# ProPrj_Analog_AI_Accelerator_2026-06-26.net
KiCad netlist of a schematic drawn in EasyEDA Pro
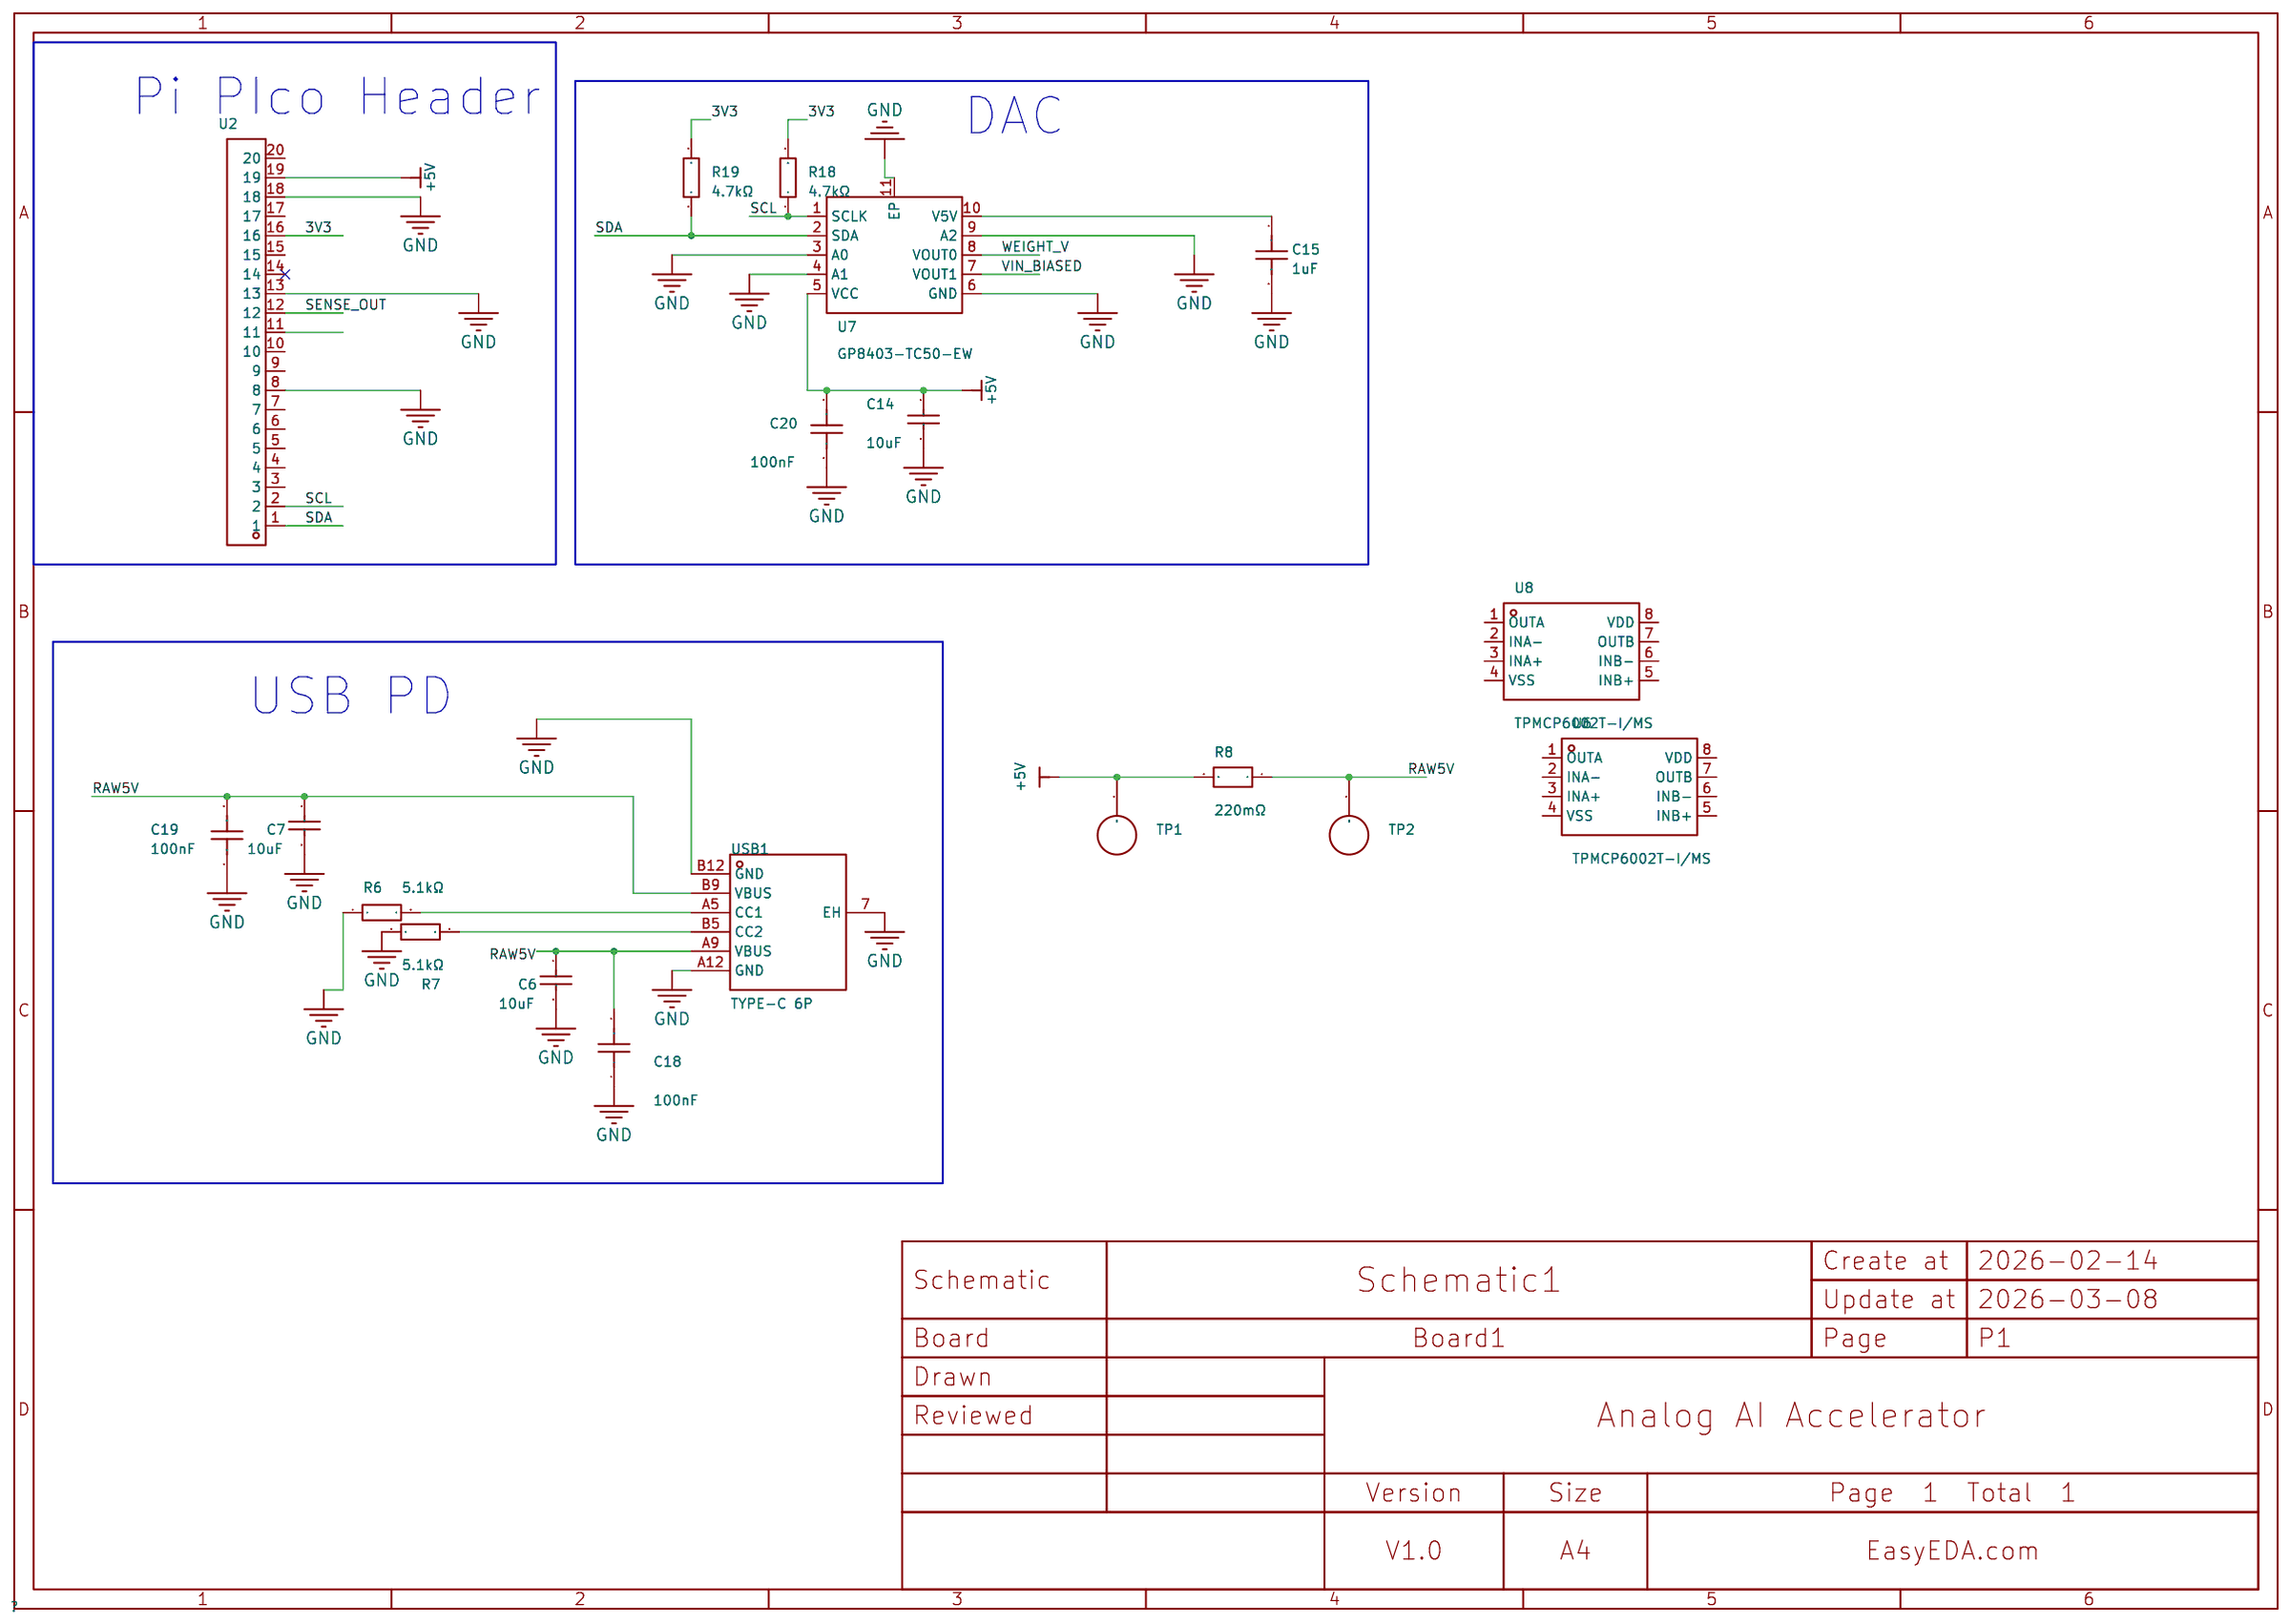
[diagram p0: schematic sheet]

(export (version "E")
  (design (tool "Eeschema 10.0.6"))
  (components
    (comp (ref "C6")
      (value "10uF")
      (footprint "easyedapro:C1206")
      (fields
        (field (name "Manufacturer Part") "CL31A106KBHNNNE")
        (field (name "Manufacturer") "SAMSUNG(三星)")
      )
      (libsource (lib "easyedapro") (part "CL31A106KBHNNNE"))
    )
    (comp (ref "C7")
      (value "10uF")
      (footprint "easyedapro:C1206")
      (fields
        (field (name "Manufacturer Part") "CL31A106KBHNNNE")
        (field (name "Manufacturer") "SAMSUNG(三星)")
      )
      (libsource (lib "easyedapro") (part "CL31A106KBHNNNE"))
    )
    (comp (ref "C14")
      (value "10uF")
      (footprint "easyedapro:C1206")
      (fields
        (field (name "Manufacturer Part") "CL31A106KBHNNNE")
        (field (name "Manufacturer") "SAMSUNG(三星)")
      )
      (libsource (lib "easyedapro") (part "CL31A106KBHNNNE"))
    )
    (comp (ref "C15")
      (value "1uF")
      (footprint "easyedapro:C1206")
      (fields
        (field (name "Manufacturer Part") "CL31B105KBHNNNE")
        (field (name "Manufacturer") "SAMSUNG(三星)")
      )
      (libsource (lib "easyedapro") (part "CL31B105KBHNNNE"))
    )
    (comp (ref "C18")
      (value "100nF")
      (footprint "easyedapro:C0603")
      (fields
        (field (name "Manufacturer Part") "CC0603KRX7R9BB104")
        (field (name "Manufacturer") "YAGEO(国巨)")
      )
      (libsource (lib "easyedapro") (part "CC0603KRX7R9BB104"))
    )
    (comp (ref "C19")
      (value "100nF")
      (footprint "easyedapro:C0603")
      (fields
        (field (name "Manufacturer Part") "CC0603KRX7R9BB104")
        (field (name "Manufacturer") "YAGEO(国巨)")
      )
      (libsource (lib "easyedapro") (part "CC0603KRX7R9BB104"))
    )
    (comp (ref "C20")
      (value "100nF")
      (footprint "easyedapro:C0603")
      (fields
        (field (name "Manufacturer Part") "CC0603KRX7R9BB104")
        (field (name "Manufacturer") "YAGEO(国巨)")
      )
      (libsource (lib "easyedapro") (part "CC0603KRX7R9BB104"))
    )
    (comp (ref "R6")
      (value "5.1kΩ")
      (footprint "easyedapro:R0603")
      (fields
        (field (name "Manufacturer Part") "0603WAF5101T5E")
        (field (name "Manufacturer") "UNI-ROYAL(厚声)")
      )
      (libsource (lib "easyedapro") (part "0603WAF5101T5E"))
    )
    (comp (ref "R7")
      (value "5.1kΩ")
      (footprint "easyedapro:R0603")
      (fields
        (field (name "Manufacturer Part") "0603WAF5101T5E")
        (field (name "Manufacturer") "UNI-ROYAL(厚声)")
      )
      (libsource (lib "easyedapro") (part "0603WAF5101T5E"))
    )
    (comp (ref "R8")
      (value "220mΩ")
      (footprint "easyedapro:RES-SMD_L6.4-W3.2-1")
      (fields
        (field (name "Manufacturer Part") "HoJLR2512-3W-220mR-1%")
        (field (name "Manufacturer") "Milliohm(毫欧)")
      )
      (libsource (lib "easyedapro") (part "HOJLR2512-3W-220MR-1%"))
    )
    (comp (ref "R18")
      (value "4.7kΩ")
      (footprint "easyedapro:R0805")
      (fields
        (field (name "Manufacturer Part") "0805W8F4701T5E")
        (field (name "Manufacturer") "UNI-ROYAL(厚声)")
      )
      (libsource (lib "easyedapro") (part "0805W8F4701T5E"))
    )
    (comp (ref "R19")
      (value "4.7kΩ")
      (footprint "easyedapro:R0805")
      (fields
        (field (name "Manufacturer Part") "0805W8F4701T5E")
        (field (name "Manufacturer") "UNI-ROYAL(厚声)")
      )
      (libsource (lib "easyedapro") (part "0805W8F4701T5E"))
    )
    (comp (ref "TP1")
      (value "~")
      (footprint "easyedapro:TEST PAD")
      (libsource (lib "easyedapro") (part "TEST PAD"))
    )
    (comp (ref "TP2")
      (value "~")
      (footprint "easyedapro:TEST PAD")
      (libsource (lib "easyedapro") (part "TEST PAD"))
    )
    (comp (ref "U2")
      (value "ZX-PM2.54-1-20PY")
      (footprint "easyedapro:HDR-TH_20P-P2.54-V-F")
      (fields (field (name "Manufacturer") "Megastar(兆星)"))
      (libsource (lib "easyedapro") (part "ZX-PM2.54-1-20PY"))
    )
    (comp (ref "U6")
      (value "TPMCP6002T-I/MS")
      (footprint "easyedapro:MSOP-8_L3.0-W3.0-P0.65-LS4.9-BL")
      (fields (field (name "Manufacturer") "TECH PUBLIC(台舟)"))
      (libsource (lib "easyedapro") (part "TPMCP6002T-I/MS"))
    )
    (comp (ref "U7")
      (value "GP8403-TC50-EW")
      (footprint "easyedapro:ESSOP-10_L4.9-W3.9-P1.00-LS6.0-BL-EP")
      (fields (field (name "Manufacturer") "Guestgood(客益)"))
      (libsource (lib "easyedapro") (part "GP8403-TC50-EW_C3152007"))
    )
    (comp (ref "U8")
      (value "TPMCP6002T-I/MS")
      (footprint "easyedapro:MSOP-8_L3.0-W3.0-P0.65-LS4.9-BL")
      (fields (field (name "Manufacturer") "TECH PUBLIC(台舟)"))
      (libsource (lib "easyedapro") (part "TPMCP6002T-I/MS"))
    )
    (comp (ref "USB1")
      (value "TYPE-C 6P")
      (footprint "easyedapro:TYPE-C-SMD_TYPE-C-6P")
      (fields (field (name "Manufacturer") "SHOU HAN(首韩)"))
      (libsource (lib "easyedapro") (part "TYPE-C 6P"))
    )
  )
  (nets
    (net (code "1") (name "+5V") (class "Default")
      (node (ref "C14") (pin "1") (pinfunction "1_1") (pintype "input"))
      (node (ref "C20") (pin "2") (pinfunction "2_2") (pintype "unspecified"))
      (node (ref "R8") (pin "2") (pinfunction "2_2") (pintype "unspecified"))
      (node (ref "TP1") (pin "1") (pinfunction "TEST_PAD1_1") (pintype "input"))
      (node (ref "U2") (pin "19") (pinfunction "19_19") (pintype "unspecified"))
      (node (ref "U7") (pin "5") (pinfunction "VCC_5") (pintype "unspecified"))
    )
    (net (code "2") (name "/3V3") (class "Default")
      (node (ref "R18") (pin "2") (pinfunction "2_2") (pintype "input"))
      (node (ref "R19") (pin "2") (pinfunction "2_2") (pintype "input"))
      (node (ref "U2") (pin "16") (pinfunction "16_16") (pintype "unspecified"))
    )
    (net (code "3") (name "/RAW5V") (class "Default")
      (node (ref "C18") (pin "2") (pinfunction "2_2") (pintype "unspecified"))
      (node (ref "C19") (pin "2") (pinfunction "2_2") (pintype "unspecified"))
      (node (ref "C6") (pin "1") (pinfunction "1_1") (pintype "input"))
      (node (ref "C7") (pin "1") (pinfunction "1_1") (pintype "input"))
      (node (ref "R8") (pin "1") (pinfunction "1_1") (pintype "unspecified"))
      (node (ref "TP2") (pin "1") (pinfunction "TEST_PAD1_1") (pintype "input"))
      (node (ref "USB1") (pin "A9") (pinfunction "VBUS_A9") (pintype "unspecified"))
      (node (ref "USB1") (pin "B9") (pinfunction "VBUS_B9") (pintype "unspecified"))
    )
    (net (code "4") (name "/SCL") (class "Default")
      (node (ref "R18") (pin "1") (pinfunction "1_1") (pintype "input"))
      (node (ref "U2") (pin "2") (pinfunction "2_2") (pintype "unspecified"))
      (node (ref "U7") (pin "1") (pinfunction "SCLK_1") (pintype "unspecified"))
    )
    (net (code "5") (name "/SDA") (class "Default")
      (node (ref "R19") (pin "1") (pinfunction "1_1") (pintype "input"))
      (node (ref "U2") (pin "1") (pinfunction "1_1") (pintype "unspecified"))
      (node (ref "U7") (pin "2") (pinfunction "SDA_2") (pintype "unspecified"))
    )
    (net (code "6") (name "/SENSE_OUT") (class "Default")
      (node (ref "U2") (pin "12") (pinfunction "12_12") (pintype "unspecified"))
    )
    (net (code "7") (name "/VIN_BIASED") (class "Default")
      (node (ref "U7") (pin "7") (pinfunction "VOUT1_7") (pintype "unspecified"))
    )
    (net (code "8") (name "/WEIGHT_V") (class "Default")
      (node (ref "U7") (pin "8") (pinfunction "VOUT0_8") (pintype "unspecified"))
    )
    (net (code "9") (name "GND") (class "Default")
      (node (ref "C14") (pin "2") (pinfunction "2_2") (pintype "input"))
      (node (ref "C15") (pin "2") (pinfunction "2_2") (pintype "unspecified"))
      (node (ref "C18") (pin "1") (pinfunction "1_1") (pintype "unspecified"))
      (node (ref "C19") (pin "1") (pinfunction "1_1") (pintype "unspecified"))
      (node (ref "C20") (pin "1") (pinfunction "1_1") (pintype "unspecified"))
      (node (ref "C6") (pin "2") (pinfunction "2_2") (pintype "input"))
      (node (ref "C7") (pin "2") (pinfunction "2_2") (pintype "input"))
      (node (ref "R6") (pin "1") (pinfunction "1_1") (pintype "input"))
      (node (ref "R7") (pin "1") (pinfunction "1_1") (pintype "input"))
      (node (ref "U2") (pin "13") (pinfunction "13_13") (pintype "unspecified"))
      (node (ref "U2") (pin "18") (pinfunction "18_18") (pintype "unspecified"))
      (node (ref "U2") (pin "8") (pinfunction "8_8") (pintype "unspecified"))
      (node (ref "U7") (pin "11") (pinfunction "EP_11") (pintype "unspecified"))
      (node (ref "U7") (pin "3") (pinfunction "A0_3") (pintype "unspecified"))
      (node (ref "U7") (pin "4") (pinfunction "A1_4") (pintype "unspecified"))
      (node (ref "U7") (pin "6") (pinfunction "GND_6") (pintype "unspecified"))
      (node (ref "U7") (pin "9") (pinfunction "A2_9") (pintype "unspecified"))
      (node (ref "USB1") (pin "7") (pinfunction "EH_7") (pintype "unspecified"))
      (node (ref "USB1") (pin "A12") (pinfunction "GND_A12") (pintype "unspecified"))
      (node (ref "USB1") (pin "B12") (pinfunction "GND_B12") (pintype "unspecified"))
    )
    (net (code "10") (name "Net-(U7-V5V)") (class "Default")
      (node (ref "C15") (pin "1") (pinfunction "1_1") (pintype "unspecified"))
      (node (ref "U7") (pin "10") (pinfunction "V5V_10") (pintype "unspecified"))
    )
    (net (code "11") (name "Net-(USB1-CC1)") (class "Default")
      (node (ref "R6") (pin "2") (pinfunction "2_2") (pintype "input"))
      (node (ref "USB1") (pin "A5") (pinfunction "CC1_A5") (pintype "unspecified"))
    )
    (net (code "12") (name "Net-(USB1-CC2)") (class "Default")
      (node (ref "R7") (pin "2") (pinfunction "2_2") (pintype "input"))
      (node (ref "USB1") (pin "B5") (pinfunction "CC2_B5") (pintype "unspecified"))
    )
    (net (code "13") (name "unconnected-(U2-Pad3)") (class "Default")
      (node (ref "U2") (pin "3") (pinfunction "3_3") (pintype "unspecified"))
    )
    (net (code "14") (name "unconnected-(U2-Pad4)") (class "Default")
      (node (ref "U2") (pin "4") (pinfunction "4_4") (pintype "unspecified"))
    )
    (net (code "15") (name "unconnected-(U2-Pad5)") (class "Default")
      (node (ref "U2") (pin "5") (pinfunction "5_5") (pintype "unspecified"))
    )
    (net (code "16") (name "unconnected-(U2-Pad6)") (class "Default")
      (node (ref "U2") (pin "6") (pinfunction "6_6") (pintype "unspecified"))
    )
    (net (code "17") (name "unconnected-(U2-Pad7)") (class "Default")
      (node (ref "U2") (pin "7") (pinfunction "7_7") (pintype "unspecified"))
    )
    (net (code "18") (name "unconnected-(U2-Pad9)") (class "Default")
      (node (ref "U2") (pin "9") (pinfunction "9_9") (pintype "unspecified"))
    )
    (net (code "19") (name "unconnected-(U2-Pad10)") (class "Default")
      (node (ref "U2") (pin "10") (pinfunction "10_10") (pintype "unspecified"))
    )
    (net (code "20") (name "unconnected-(U2-Pad11)") (class "Default")
      (node (ref "U2") (pin "11") (pinfunction "11_11") (pintype "unspecified"))
    )
    (net (code "21") (name "unconnected-(U2-Pad14)") (class "Default")
      (node (ref "U2") (pin "14") (pinfunction "14_14") (pintype "unspecified+no_connect"))
    )
    (net (code "22") (name "unconnected-(U2-Pad15)") (class "Default")
      (node (ref "U2") (pin "15") (pinfunction "15_15") (pintype "unspecified"))
    )
    (net (code "23") (name "unconnected-(U2-Pad17)") (class "Default")
      (node (ref "U2") (pin "17") (pinfunction "17_17") (pintype "unspecified"))
    )
    (net (code "24") (name "unconnected-(U2-Pad20)") (class "Default")
      (node (ref "U2") (pin "20") (pinfunction "20_20") (pintype "unspecified"))
    )
    (net (code "25") (name "unconnected-(U6-INA+-Pad3)") (class "Default")
      (node (ref "U6") (pin "3") (pinfunction "INA+_3") (pintype "unspecified"))
    )
    (net (code "26") (name "unconnected-(U6-INA--Pad2)") (class "Default")
      (node (ref "U6") (pin "2") (pinfunction "INA-_2") (pintype "unspecified"))
    )
    (net (code "27") (name "unconnected-(U6-INB+-Pad5)") (class "Default")
      (node (ref "U6") (pin "5") (pinfunction "INB+_5") (pintype "unspecified"))
    )
    (net (code "28") (name "unconnected-(U6-INB--Pad6)") (class "Default")
      (node (ref "U6") (pin "6") (pinfunction "INB-_6") (pintype "unspecified"))
    )
    (net (code "29") (name "unconnected-(U6-OUTA-Pad1)") (class "Default")
      (node (ref "U6") (pin "1") (pinfunction "OUTA_1") (pintype "unspecified"))
    )
    (net (code "30") (name "unconnected-(U6-OUTB-Pad7)") (class "Default")
      (node (ref "U6") (pin "7") (pinfunction "OUTB_7") (pintype "unspecified"))
    )
    (net (code "31") (name "unconnected-(U6-VDD-Pad8)") (class "Default")
      (node (ref "U6") (pin "8") (pinfunction "VDD_8") (pintype "unspecified"))
    )
    (net (code "32") (name "unconnected-(U6-VSS-Pad4)") (class "Default")
      (node (ref "U6") (pin "4") (pinfunction "VSS_4") (pintype "unspecified"))
    )
    (net (code "33") (name "unconnected-(U8-INA+-Pad3)") (class "Default")
      (node (ref "U8") (pin "3") (pinfunction "INA+_3") (pintype "unspecified"))
    )
    (net (code "34") (name "unconnected-(U8-INA--Pad2)") (class "Default")
      (node (ref "U8") (pin "2") (pinfunction "INA-_2") (pintype "unspecified"))
    )
    (net (code "35") (name "unconnected-(U8-INB+-Pad5)") (class "Default")
      (node (ref "U8") (pin "5") (pinfunction "INB+_5") (pintype "unspecified"))
    )
    (net (code "36") (name "unconnected-(U8-INB--Pad6)") (class "Default")
      (node (ref "U8") (pin "6") (pinfunction "INB-_6") (pintype "unspecified"))
    )
    (net (code "37") (name "unconnected-(U8-OUTA-Pad1)") (class "Default")
      (node (ref "U8") (pin "1") (pinfunction "OUTA_1") (pintype "unspecified"))
    )
    (net (code "38") (name "unconnected-(U8-OUTB-Pad7)") (class "Default")
      (node (ref "U8") (pin "7") (pinfunction "OUTB_7") (pintype "unspecified"))
    )
    (net (code "39") (name "unconnected-(U8-VDD-Pad8)") (class "Default")
      (node (ref "U8") (pin "8") (pinfunction "VDD_8") (pintype "unspecified"))
    )
    (net (code "40") (name "unconnected-(U8-VSS-Pad4)") (class "Default")
      (node (ref "U8") (pin "4") (pinfunction "VSS_4") (pintype "unspecified"))
    )
  )
)
